# design.net
KiCad netlist of a schematic drawn in EAGLE
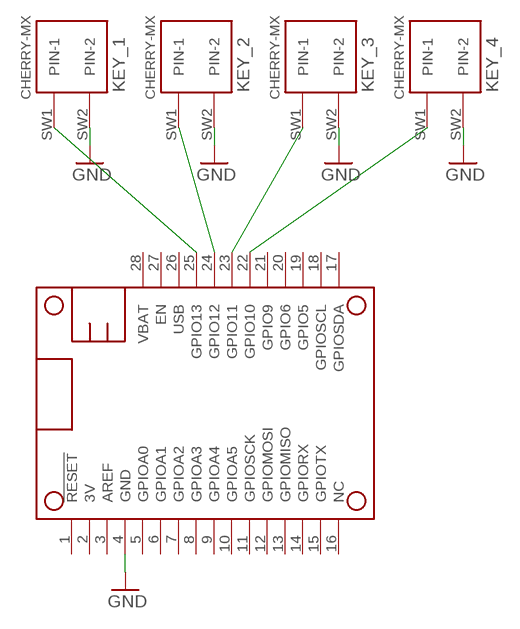
[diagram p0: schematic, sheet 1]

(export (version "E")
  (design (tool "Eeschema 10.0.6"))
  (components
    (comp (ref "KEY_1")
      (value "CHERRY-MX")
      (footprint "eagle-import:CHERRY-MX")
      (libsource (lib "eagle-import") (part "CHERRY-MX"))
    )
    (comp (ref "KEY_2")
      (value "CHERRY-MX")
      (footprint "eagle-import:CHERRY-MX")
      (libsource (lib "eagle-import") (part "CHERRY-MX"))
    )
    (comp (ref "KEY_3")
      (value "CHERRY-MX")
      (footprint "eagle-import:CHERRY-MX")
      (libsource (lib "eagle-import") (part "CHERRY-MX"))
    )
    (comp (ref "KEY_4")
      (value "CHERRY-MX")
      (footprint "eagle-import:CHERRY-MX")
      (libsource (lib "eagle-import") (part "CHERRY-MX"))
    )
    (comp (ref "MS1")
      (value "FEATHERWING_NODIM")
      (footprint "eagle-import:FEATHERWING_DIM")
      (libsource (lib "eagle-import") (part "FEATHERWING_NODIM"))
    )
  )
  (nets
    (net (code "1") (name "/3V") (class "Default")
      (node (ref "MS1") (pin "2") (pinfunction "3V_2") (pintype "power_in"))
    )
    (net (code "2") (name "/USB") (class "Default")
      (node (ref "MS1") (pin "26") (pinfunction "USB_26") (pintype "power_in"))
    )
    (net (code "3") (name "/VBAT") (class "Default")
      (node (ref "MS1") (pin "28") (pinfunction "VBAT_28") (pintype "power_in"))
    )
    (net (code "4") (name "GND") (class "Default")
      (node (ref "KEY_1") (pin "SW2") (pinfunction "PIN-2_SW2") (pintype "bidirectional"))
      (node (ref "KEY_2") (pin "SW2") (pinfunction "PIN-2_SW2") (pintype "bidirectional"))
      (node (ref "KEY_3") (pin "SW2") (pinfunction "PIN-2_SW2") (pintype "bidirectional"))
      (node (ref "KEY_4") (pin "SW2") (pinfunction "PIN-2_SW2") (pintype "bidirectional"))
      (node (ref "MS1") (pin "4") (pinfunction "GND_4") (pintype "power_in"))
    )
    (net (code "5") (name "Net-(KEY_1-PIN-1)") (class "Default")
      (node (ref "KEY_1") (pin "SW1") (pinfunction "PIN-1_SW1") (pintype "bidirectional"))
      (node (ref "MS1") (pin "25") (pinfunction "GPIO13_25") (pintype "bidirectional"))
    )
    (net (code "6") (name "Net-(KEY_2-PIN-1)") (class "Default")
      (node (ref "KEY_2") (pin "SW1") (pinfunction "PIN-1_SW1") (pintype "bidirectional"))
      (node (ref "MS1") (pin "24") (pinfunction "GPIO12_24") (pintype "bidirectional"))
    )
    (net (code "7") (name "Net-(KEY_3-PIN-1)") (class "Default")
      (node (ref "KEY_3") (pin "SW1") (pinfunction "PIN-1_SW1") (pintype "bidirectional"))
      (node (ref "MS1") (pin "23") (pinfunction "GPIO11_23") (pintype "bidirectional"))
    )
    (net (code "8") (name "Net-(KEY_4-PIN-1)") (class "Default")
      (node (ref "KEY_4") (pin "SW1") (pinfunction "PIN-1_SW1") (pintype "bidirectional"))
      (node (ref "MS1") (pin "22") (pinfunction "GPIO10_22") (pintype "bidirectional"))
    )
    (net (code "9") (name "unconnected-(MS1-AREF-Pad3)") (class "Default")
      (node (ref "MS1") (pin "3") (pinfunction "AREF_3") (pintype "passive"))
    )
    (net (code "10") (name "unconnected-(MS1-EN-Pad27)") (class "Default")
      (node (ref "MS1") (pin "27") (pinfunction "EN_27") (pintype "passive"))
    )
    (net (code "11") (name "unconnected-(MS1-GPIO5-Pad19)") (class "Default")
      (node (ref "MS1") (pin "19") (pinfunction "GPIO5_19") (pintype "bidirectional"))
    )
    (net (code "12") (name "unconnected-(MS1-GPIO6-Pad20)") (class "Default")
      (node (ref "MS1") (pin "20") (pinfunction "GPIO6_20") (pintype "bidirectional"))
    )
    (net (code "13") (name "unconnected-(MS1-GPIO9-Pad21)") (class "Default")
      (node (ref "MS1") (pin "21") (pinfunction "GPIO9_21") (pintype "bidirectional"))
    )
    (net (code "14") (name "unconnected-(MS1-GPIOA0-Pad5)") (class "Default")
      (node (ref "MS1") (pin "5") (pinfunction "GPIOA0_5") (pintype "bidirectional"))
    )
    (net (code "15") (name "unconnected-(MS1-GPIOA1-Pad6)") (class "Default")
      (node (ref "MS1") (pin "6") (pinfunction "GPIOA1_6") (pintype "bidirectional"))
    )
    (net (code "16") (name "unconnected-(MS1-GPIOA2-Pad7)") (class "Default")
      (node (ref "MS1") (pin "7") (pinfunction "GPIOA2_7") (pintype "bidirectional"))
    )
    (net (code "17") (name "unconnected-(MS1-GPIOA3-Pad8)") (class "Default")
      (node (ref "MS1") (pin "8") (pinfunction "GPIOA3_8") (pintype "bidirectional"))
    )
    (net (code "18") (name "unconnected-(MS1-GPIOA4-Pad9)") (class "Default")
      (node (ref "MS1") (pin "9") (pinfunction "GPIOA4_9") (pintype "bidirectional"))
    )
    (net (code "19") (name "unconnected-(MS1-GPIOA5-Pad10)") (class "Default")
      (node (ref "MS1") (pin "10") (pinfunction "GPIOA5_10") (pintype "bidirectional"))
    )
    (net (code "20") (name "unconnected-(MS1-GPIOMISO-Pad13)") (class "Default")
      (node (ref "MS1") (pin "13") (pinfunction "GPIOMISO_13") (pintype "bidirectional"))
    )
    (net (code "21") (name "unconnected-(MS1-GPIOMOSI-Pad12)") (class "Default")
      (node (ref "MS1") (pin "12") (pinfunction "GPIOMOSI_12") (pintype "bidirectional"))
    )
    (net (code "22") (name "unconnected-(MS1-GPIORX-Pad14)") (class "Default")
      (node (ref "MS1") (pin "14") (pinfunction "GPIORX_14") (pintype "bidirectional"))
    )
    (net (code "23") (name "unconnected-(MS1-GPIOSCK-Pad11)") (class "Default")
      (node (ref "MS1") (pin "11") (pinfunction "GPIOSCK_11") (pintype "bidirectional"))
    )
    (net (code "24") (name "unconnected-(MS1-GPIOSCL-Pad18)") (class "Default")
      (node (ref "MS1") (pin "18") (pinfunction "GPIOSCL_18") (pintype "bidirectional"))
    )
    (net (code "25") (name "unconnected-(MS1-GPIOSDA-Pad17)") (class "Default")
      (node (ref "MS1") (pin "17") (pinfunction "GPIOSDA_17") (pintype "bidirectional"))
    )
    (net (code "26") (name "unconnected-(MS1-GPIOTX-Pad15)") (class "Default")
      (node (ref "MS1") (pin "15") (pinfunction "GPIOTX_15") (pintype "bidirectional"))
    )
    (net (code "27") (name "unconnected-(MS1-NC-Pad16)") (class "Default")
      (node (ref "MS1") (pin "16") (pinfunction "NC_16") (pintype "passive"))
    )
    (net (code "28") (name "unconnected-(MS1-~{RESET}-Pad1)") (class "Default")
      (node (ref "MS1") (pin "1") (pinfunction "~{RESET}_1") (pintype "input"))
    )
  )
)
